# brain_rev_2.net
KiCad netlist of a schematic drawn in EAGLE
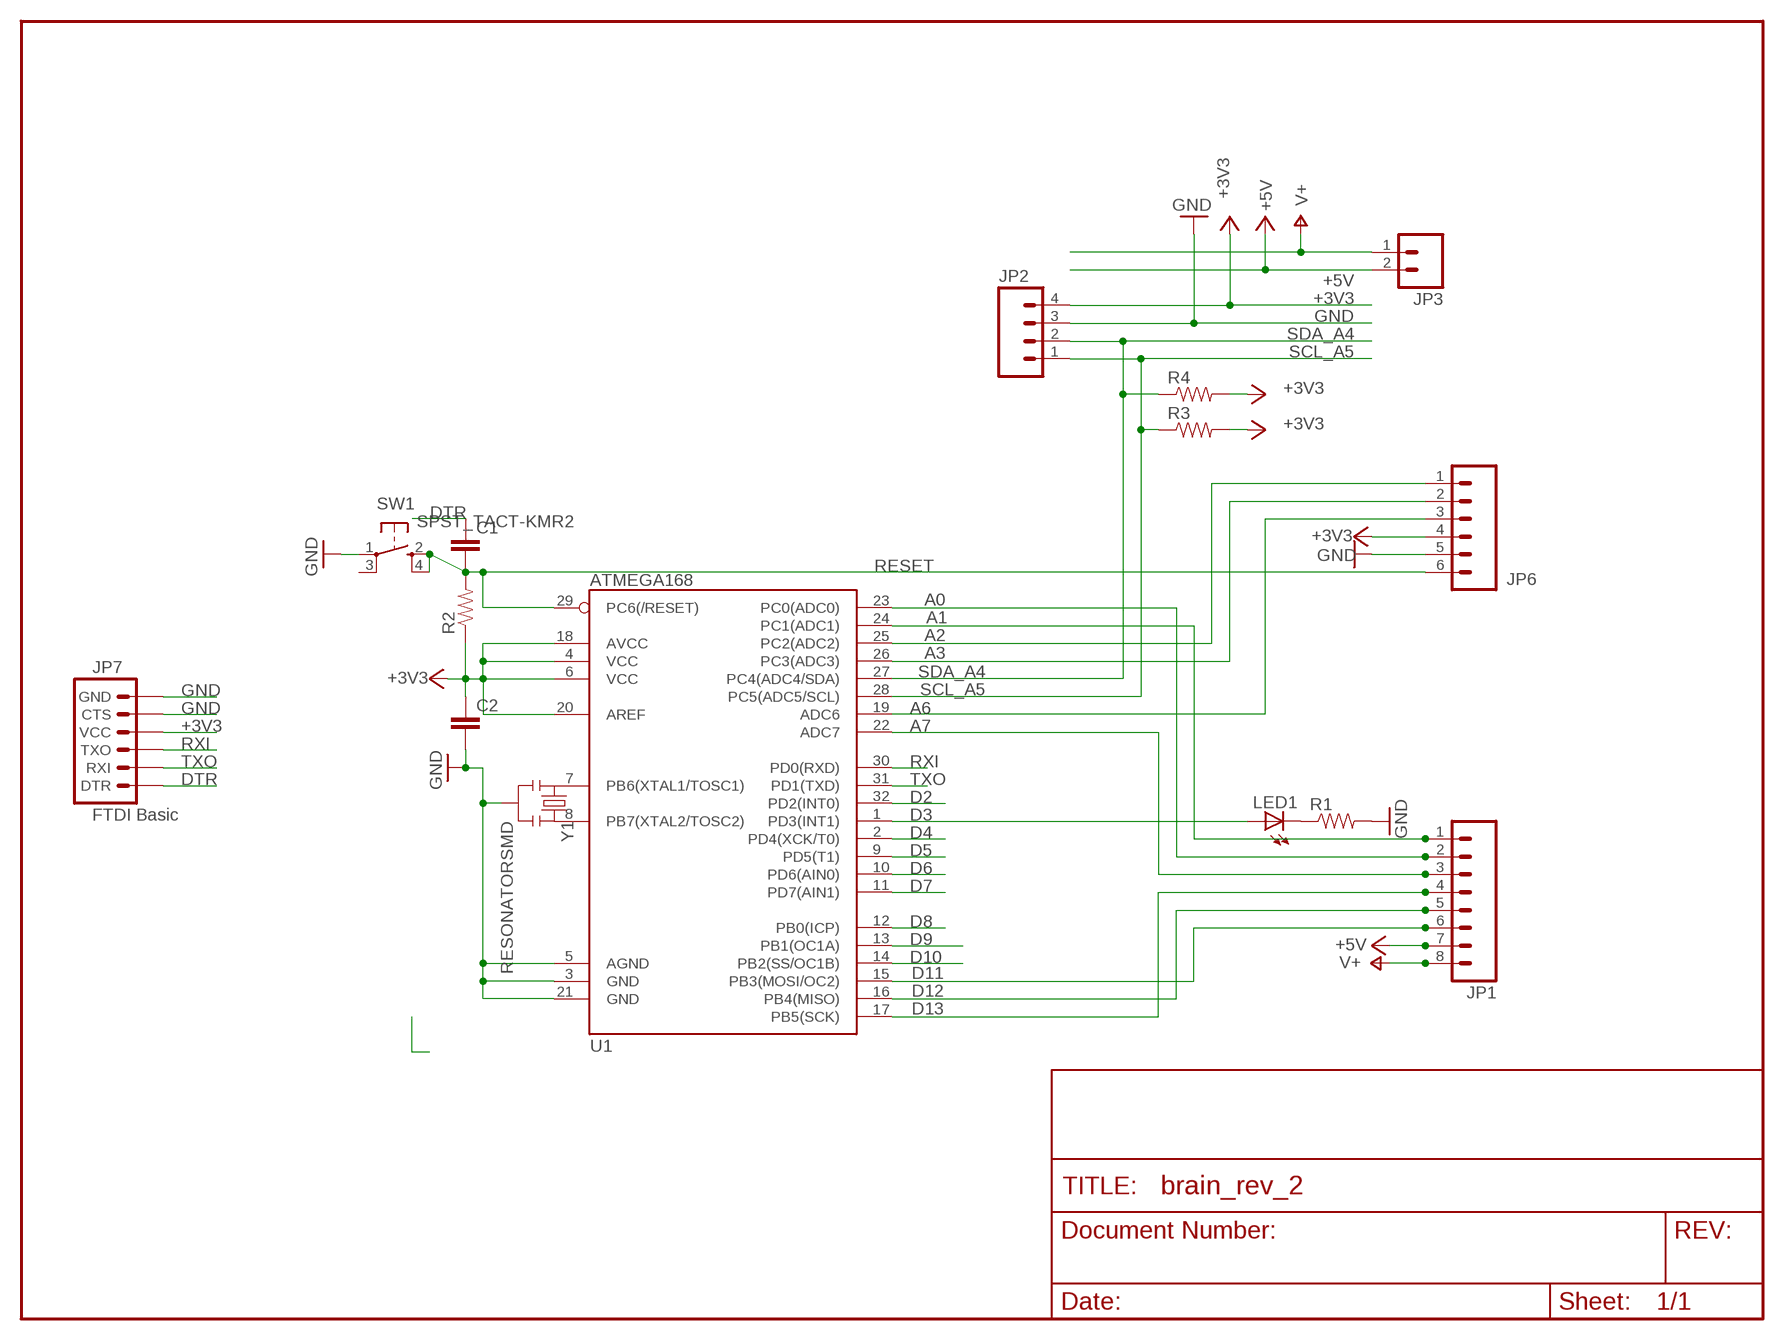
[diagram p0: schematic, sheet 1]

(export (version "E")
  (design (tool "Eeschema 10.0.6"))
  (components
    (comp (ref "C1")
      (value "CAP1206")
      (footprint "eagle-import:1206")
      (libsource (lib "eagle-import") (part "CAP1206"))
    )
    (comp (ref "C2")
      (value "CAP1206")
      (footprint "eagle-import:1206")
      (libsource (lib "eagle-import") (part "CAP1206"))
    )
    (comp (ref "JP1")
      (value "M081X08")
      (footprint "eagle-import:1X08")
      (libsource (lib "eagle-import") (part "M081X08"))
    )
    (comp (ref "JP2")
      (value "M04PTH")
      (footprint "eagle-import:1X04")
      (libsource (lib "eagle-import") (part "M04PTH"))
    )
    (comp (ref "JP3")
      (value "M02PTH")
      (footprint "eagle-import:1X02")
      (libsource (lib "eagle-import") (part "M02PTH"))
    )
    (comp (ref "JP6")
      (value "M06SIP")
      (footprint "eagle-import:1X06")
      (libsource (lib "eagle-import") (part "M06SIP"))
    )
    (comp (ref "JP7")
      (value "FTDI Basic")
      (footprint "eagle-import:1X06")
      (libsource (lib "eagle-import") (part "ARDUINO_SERIAL_PROGRAMPTH"))
    )
    (comp (ref "LED1")
      (value "LEDCHIPLED_1206")
      (footprint "eagle-import:CHIPLED_1206")
      (libsource (lib "eagle-import") (part "LEDCHIPLED_1206"))
    )
    (comp (ref "R1")
      (value "RESISTOR1206")
      (footprint "eagle-import:1206")
      (libsource (lib "eagle-import") (part "RESISTOR1206"))
    )
    (comp (ref "R2")
      (value "RESISTOR1206")
      (footprint "eagle-import:1206")
      (libsource (lib "eagle-import") (part "RESISTOR1206"))
    )
    (comp (ref "R3")
      (value "RESISTOR1206")
      (footprint "eagle-import:1206")
      (libsource (lib "eagle-import") (part "RESISTOR1206"))
    )
    (comp (ref "R4")
      (value "RESISTOR1206")
      (footprint "eagle-import:1206")
      (libsource (lib "eagle-import") (part "RESISTOR1206"))
    )
    (comp (ref "SW1")
      (value "SPST_TACT-KMR2")
      (footprint "eagle-import:KMR2")
      (libsource (lib "eagle-import") (part "SPST_TACT-KMR2"))
    )
    (comp (ref "U1")
      (value "ATMEGA168")
      (footprint "eagle-import:TQFP32-08")
      (libsource (lib "eagle-import") (part "ATMEGA168"))
    )
    (comp (ref "Y1")
      (value "RESONATORSMD")
      (footprint "eagle-import:RESONATOR-SMD")
      (libsource (lib "eagle-import") (part "RESONATORSMD"))
    )
  )
  (nets
    (net (code "1") (name "+3V3") (class "Default")
      (node (ref "C2") (pin "1") (pinfunction "1_1") (pintype "passive"))
      (node (ref "JP2") (pin "4") (pinfunction "4_4") (pintype "passive"))
      (node (ref "JP6") (pin "4") (pinfunction "4_4") (pintype "passive"))
      (node (ref "JP7") (pin "4") (pinfunction "VCC_4") (pintype "passive"))
      (node (ref "R2") (pin "1") (pinfunction "1_1") (pintype "passive"))
      (node (ref "R3") (pin "2") (pinfunction "2_2") (pintype "passive"))
      (node (ref "R4") (pin "2") (pinfunction "2_2") (pintype "passive"))
      (node (ref "U1") (pin "18") (pinfunction "AVCC_18") (pintype "bidirectional"))
      (node (ref "U1") (pin "20") (pinfunction "AREF_20") (pintype "bidirectional"))
      (node (ref "U1") (pin "4") (pinfunction "VCC_4") (pintype "bidirectional"))
      (node (ref "U1") (pin "6") (pinfunction "VCC_6") (pintype "bidirectional"))
    )
    (net (code "2") (name "+5V") (class "Default")
      (node (ref "JP1") (pin "7") (pinfunction "7_7") (pintype "passive"))
      (node (ref "JP3") (pin "2") (pinfunction "2_2") (pintype "passive"))
    )
    (net (code "3") (name "/A0") (class "Default")
      (node (ref "JP1") (pin "2") (pinfunction "2_2") (pintype "passive"))
      (node (ref "U1") (pin "23") (pinfunction "PC0(ADC0)_23") (pintype "bidirectional"))
    )
    (net (code "4") (name "/A1") (class "Default")
      (node (ref "JP1") (pin "1") (pinfunction "1_1") (pintype "passive"))
      (node (ref "U1") (pin "24") (pinfunction "PC1(ADC1)_24") (pintype "bidirectional"))
    )
    (net (code "5") (name "/A2") (class "Default")
      (node (ref "JP6") (pin "1") (pinfunction "1_1") (pintype "passive"))
      (node (ref "U1") (pin "25") (pinfunction "PC2(ADC2)_25") (pintype "bidirectional"))
    )
    (net (code "6") (name "/A3") (class "Default")
      (node (ref "JP6") (pin "2") (pinfunction "2_2") (pintype "passive"))
      (node (ref "U1") (pin "26") (pinfunction "PC3(ADC3)_26") (pintype "bidirectional"))
    )
    (net (code "7") (name "/A6") (class "Default")
      (node (ref "JP6") (pin "3") (pinfunction "3_3") (pintype "passive"))
      (node (ref "U1") (pin "19") (pinfunction "ADC6_19") (pintype "bidirectional"))
    )
    (net (code "8") (name "/A7") (class "Default")
      (node (ref "JP1") (pin "3") (pinfunction "3_3") (pintype "passive"))
      (node (ref "U1") (pin "22") (pinfunction "ADC7_22") (pintype "bidirectional"))
    )
    (net (code "9") (name "/D2") (class "Default")
      (node (ref "U1") (pin "32") (pinfunction "PD2(INT0)_32") (pintype "bidirectional"))
    )
    (net (code "10") (name "/D3") (class "Default")
      (node (ref "LED1") (pin "A") (pinfunction "A_A") (pintype "passive"))
      (node (ref "U1") (pin "1") (pinfunction "PD3(INT1)_1") (pintype "bidirectional"))
    )
    (net (code "11") (name "/D4") (class "Default")
      (node (ref "U1") (pin "2") (pinfunction "PD4(XCK/T0)_2") (pintype "bidirectional"))
    )
    (net (code "12") (name "/D5") (class "Default")
      (node (ref "U1") (pin "9") (pinfunction "PD5(T1)_9") (pintype "bidirectional"))
    )
    (net (code "13") (name "/D6") (class "Default")
      (node (ref "U1") (pin "10") (pinfunction "PD6(AIN0)_10") (pintype "bidirectional"))
    )
    (net (code "14") (name "/D7") (class "Default")
      (node (ref "U1") (pin "11") (pinfunction "PD7(AIN1)_11") (pintype "bidirectional"))
    )
    (net (code "15") (name "/D8") (class "Default")
      (node (ref "U1") (pin "12") (pinfunction "PB0(ICP)_12") (pintype "bidirectional"))
    )
    (net (code "16") (name "/D9") (class "Default")
      (node (ref "U1") (pin "13") (pinfunction "PB1(OC1A)_13") (pintype "bidirectional"))
    )
    (net (code "17") (name "/D10") (class "Default")
      (node (ref "U1") (pin "14") (pinfunction "PB2(SS/OC1B)_14") (pintype "bidirectional"))
    )
    (net (code "18") (name "/D11") (class "Default")
      (node (ref "JP1") (pin "6") (pinfunction "6_6") (pintype "passive"))
      (node (ref "U1") (pin "15") (pinfunction "PB3(MOSI/OC2)_15") (pintype "bidirectional"))
    )
    (net (code "19") (name "/D12") (class "Default")
      (node (ref "JP1") (pin "5") (pinfunction "5_5") (pintype "passive"))
      (node (ref "U1") (pin "16") (pinfunction "PB4(MISO)_16") (pintype "bidirectional"))
    )
    (net (code "20") (name "/D13") (class "Default")
      (node (ref "JP1") (pin "4") (pinfunction "4_4") (pintype "passive"))
      (node (ref "U1") (pin "17") (pinfunction "PB5(SCK)_17") (pintype "bidirectional"))
    )
    (net (code "21") (name "/DTR") (class "Default")
      (node (ref "C1") (pin "1") (pinfunction "1_1") (pintype "passive"))
      (node (ref "JP7") (pin "1") (pinfunction "DTR_1") (pintype "passive"))
    )
    (net (code "22") (name "/RESET") (class "Default")
      (node (ref "C1") (pin "2") (pinfunction "2_2") (pintype "passive"))
      (node (ref "JP6") (pin "6") (pinfunction "6_6") (pintype "passive"))
      (node (ref "R2") (pin "2") (pinfunction "2_2") (pintype "passive"))
      (node (ref "SW1") (pin "2") (pinfunction "S_2") (pintype "passive"))
      (node (ref "SW1") (pin "4") (pinfunction "S1_4") (pintype "passive"))
      (node (ref "U1") (pin "29") (pinfunction "PC6(/RESET)_29") (pintype "bidirectional"))
    )
    (net (code "23") (name "/RXI") (class "Default")
      (node (ref "JP7") (pin "3") (pinfunction "TXO_3") (pintype "passive"))
      (node (ref "U1") (pin "30") (pinfunction "PD0(RXD)_30") (pintype "bidirectional"))
    )
    (net (code "24") (name "/SCL_A5") (class "Default")
      (node (ref "JP2") (pin "1") (pinfunction "1_1") (pintype "passive"))
      (node (ref "R3") (pin "1") (pinfunction "1_1") (pintype "passive"))
      (node (ref "U1") (pin "28") (pinfunction "PC5(ADC5/SCL)_28") (pintype "bidirectional"))
    )
    (net (code "25") (name "/SDA_A4") (class "Default")
      (node (ref "JP2") (pin "2") (pinfunction "2_2") (pintype "passive"))
      (node (ref "R4") (pin "1") (pinfunction "1_1") (pintype "passive"))
      (node (ref "U1") (pin "27") (pinfunction "PC4(ADC4/SDA)_27") (pintype "bidirectional"))
    )
    (net (code "26") (name "/TXO") (class "Default")
      (node (ref "JP7") (pin "2") (pinfunction "RXI_2") (pintype "passive"))
      (node (ref "U1") (pin "31") (pinfunction "PD1(TXD)_31") (pintype "bidirectional"))
    )
    (net (code "27") (name "GND") (class "Default")
      (node (ref "C2") (pin "2") (pinfunction "2_2") (pintype "passive"))
      (node (ref "JP2") (pin "3") (pinfunction "3_3") (pintype "passive"))
      (node (ref "JP6") (pin "5") (pinfunction "5_5") (pintype "passive"))
      (node (ref "JP7") (pin "5") (pinfunction "CTS_5") (pintype "passive"))
      (node (ref "JP7") (pin "6") (pinfunction "GND_6") (pintype "passive"))
      (node (ref "R1") (pin "2") (pinfunction "2_2") (pintype "passive"))
      (node (ref "SW1") (pin "1") (pinfunction "P_1") (pintype "passive"))
      (node (ref "U1") (pin "21") (pinfunction "GND_21") (pintype "bidirectional"))
      (node (ref "U1") (pin "3") (pinfunction "GND_3") (pintype "bidirectional"))
      (node (ref "U1") (pin "5") (pinfunction "AGND_5") (pintype "bidirectional"))
      (node (ref "Y1") (pin "2") (pinfunction "2_2") (pintype "passive"))
    )
    (net (code "28") (name "Net-(LED1-PadC)") (class "Default")
      (node (ref "LED1") (pin "C") (pinfunction "C_C") (pintype "passive"))
      (node (ref "R1") (pin "1") (pinfunction "1_1") (pintype "passive"))
    )
    (net (code "29") (name "Net-(U1-PB6(XTAL1{slash}TOSC1))") (class "Default")
      (node (ref "U1") (pin "7") (pinfunction "PB6(XTAL1/TOSC1)_7") (pintype "bidirectional"))
      (node (ref "Y1") (pin "1") (pinfunction "1_1") (pintype "passive"))
    )
    (net (code "30") (name "Net-(U1-PB7(XTAL2{slash}TOSC2))") (class "Default")
      (node (ref "U1") (pin "8") (pinfunction "PB7(XTAL2/TOSC2)_8") (pintype "bidirectional"))
      (node (ref "Y1") (pin "3") (pinfunction "3_3") (pintype "passive"))
    )
    (net (code "31") (name "V+") (class "Default")
      (node (ref "JP1") (pin "8") (pinfunction "8_8") (pintype "passive"))
      (node (ref "JP3") (pin "1") (pinfunction "1_1") (pintype "passive"))
    )
    (net (code "32") (name "unconnected-(SW1-P1-Pad3)") (class "Default")
      (node (ref "SW1") (pin "3") (pinfunction "P1_3") (pintype "passive"))
    )
  )
)
